# GateDriver.net
KiCad netlist of a schematic drawn in Altium Designer
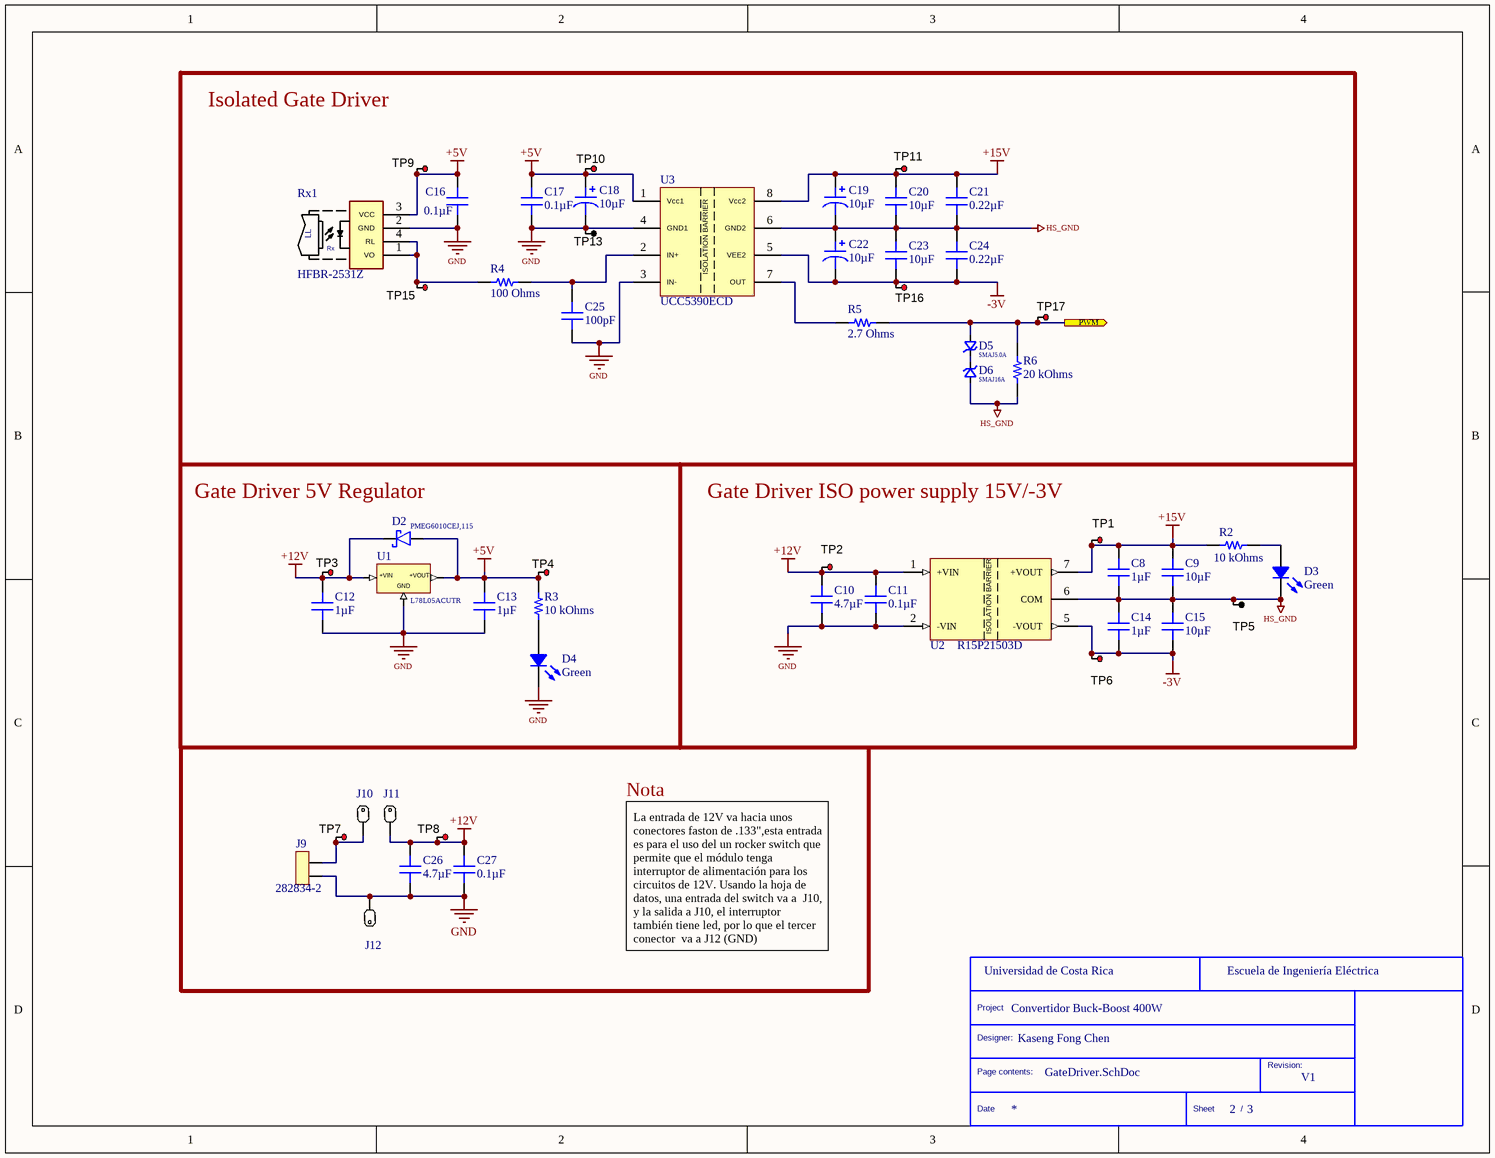
[diagram p0: GateDriver.SchDoc]

(export (version "E")
  (design (tool "Eeschema 10.0.6"))
  (components
    (comp (ref "C8")
      (value "1µF")
      (footprint "CAP 0603_1608")
      (description "CAP CER 1UF 50V X7R 0603")
      (fields (field (name "PART NUMBER") "UMK107AB7105KA-T") (field (name "MANUFACTURER") "Taiyo Yuden"))
      (libsource (lib "Celestial Altium Library - altium_library") (part "Capacitor"))
    )
    (comp (ref "C9")
      (value "10µF")
      (footprint "CAP 1206_3216 - 1.8MM")
      (description "CAP CER 10UF 25V X7R 1206")
      (fields (field (name "PART NUMBER") "TMK316AB7106KL-T") (field (name "MANUFACTURER") "Taiyo Yuden"))
      (libsource (lib "Celestial Altium Library - altium_library") (part "Capacitor"))
    )
    (comp (ref "C10")
      (value "4.7µF")
      (footprint "CAP 1206_3216 - 1.8MM")
      (description "CAP CER 4.7UF 50V X7R 1206")
      (fields (field (name "PART NUMBER") "UMK316AB7475KL-T") (field (name "MANUFACTURER") "Taiyo Yuden"))
      (libsource (lib "Celestial Altium Library - altium_library") (part "Capacitor"))
    )
    (comp (ref "C11")
      (value "0.1µF")
      (footprint "CAP 0603_1608")
      (description "CAP CER 0.1UF 50V X7R 0603")
      (fields (field (name "PART NUMBER") "C0603C104M5RACTU") (field (name "MANUFACTURER") "KEMET"))
      (libsource (lib "Celestial Altium Library - altium_library") (part "Capacitor"))
    )
    (comp (ref "C12")
      (value "1µF")
      (footprint "CAP 0603_1608")
      (description "CAP CER 1UF 25V X7R 0603")
      (fields (field (name "PART NUMBER") "TMK107B7105KA-T") (field (name "MANUFACTURER") "Taiyo Yuden"))
      (libsource (lib "Celestial Altium Library - altium_library") (part "Capacitor"))
    )
    (comp (ref "C13")
      (value "1µF")
      (footprint "CAP 0603_1608")
      (description "CAP CER 1UF 16V X7R 0603")
      (fields (field (name "PART NUMBER") "CC0603KRX7R7BB105") (field (name "MANUFACTURER") "Yageo"))
      (libsource (lib "Celestial Altium Library - altium_library") (part "Capacitor"))
    )
    (comp (ref "C14")
      (value "1µF")
      (footprint "CAP 0603_1608")
      (description "CAP CER 1UF 50V X7R 0603")
      (fields (field (name "PART NUMBER") "UMK107AB7105KA-T") (field (name "MANUFACTURER") "Taiyo Yuden"))
      (libsource (lib "Celestial Altium Library - altium_library") (part "Capacitor"))
    )
    (comp (ref "C15")
      (value "10µF")
      (footprint "CAP 1206_3216 - 1.8MM")
      (description "CAP CER 10UF 25V X7R 1206")
      (fields (field (name "PART NUMBER") "TMK316AB7106KL-T") (field (name "MANUFACTURER") "Taiyo Yuden"))
      (libsource (lib "Celestial Altium Library - altium_library") (part "Capacitor"))
    )
    (comp (ref "C16")
      (value "0.1µF")
      (footprint "CAP 0603_1608")
      (description "CAP CER 0.1UF 50V X7R 0603")
      (fields (field (name "PART NUMBER") "C0603C104M5RACTU") (field (name "MANUFACTURER") "KEMET"))
      (libsource (lib "Celestial Altium Library - altium_library") (part "Capacitor"))
    )
    (comp (ref "C17")
      (value "0.1µF")
      (footprint "CAP 0603_1608")
      (description "CAP CER 0.1UF 50V X7R 0603")
      (fields (field (name "PART NUMBER") "C0603C104M5RACTU") (field (name "MANUFACTURER") "KEMET"))
      (libsource (lib "Celestial Altium Library - altium_library") (part "Capacitor"))
    )
    (comp (ref "C18")
      (value "10µF")
      (footprint "CAP POL 2917_7343")
      (description "CAP TANT 10UF 10% 50V 2917")
      (fields (field (name "PART NUMBER") "T491D106K050AT") (field (name "MANUFACTURER") "KEMET"))
      (libsource (lib "Celestial Altium Library - altium_library") (part "Polarised Capacitor"))
    )
    (comp (ref "C19")
      (value "10µF")
      (footprint "CAP POL 2917_7343")
      (description "CAP TANT 10UF 10% 50V 2917")
      (fields (field (name "PART NUMBER") "T491D106K050AT") (field (name "MANUFACTURER") "KEMET"))
      (libsource (lib "Celestial Altium Library - altium_library") (part "Polarised Capacitor"))
    )
    (comp (ref "C20")
      (value "10µF")
      (footprint "CAP 1210_3225 - 2.8MM")
      (description "CAP CER 10UF 50V X7S 1210")
      (fields (field (name "PART NUMBER") "UMK325C7106MM-T") (field (name "MANUFACTURER") "Taiyo Yuden"))
      (libsource (lib "Celestial Altium Library - altium_library") (part "Capacitor"))
    )
    (comp (ref "C21")
      (value "0.22µF")
      (footprint "CAP 0805_2012")
      (description "CAP CER 0.22UF 50V X7R 0805")
      (fields (field (name "PART NUMBER") "UMK212B7224KG-T") (field (name "MANUFACTURER") "Taiyo Yuden"))
      (libsource (lib "Celestial Altium Library - altium_library") (part "Capacitor"))
    )
    (comp (ref "C22")
      (value "10µF")
      (footprint "CAP POL 2917_7343")
      (description "CAP TANT 10UF 10% 50V 2917")
      (fields (field (name "PART NUMBER") "T491D106K050AT") (field (name "MANUFACTURER") "KEMET"))
      (libsource (lib "Celestial Altium Library - altium_library") (part "Polarised Capacitor"))
    )
    (comp (ref "C23")
      (value "10µF")
      (footprint "CAP 1210_3225 - 2.8MM")
      (description "CAP CER 10UF 50V X7S 1210")
      (fields (field (name "PART NUMBER") "UMK325C7106MM-T") (field (name "MANUFACTURER") "Taiyo Yuden"))
      (libsource (lib "Celestial Altium Library - altium_library") (part "Capacitor"))
    )
    (comp (ref "C24")
      (value "0.22µF")
      (footprint "CAP 0805_2012")
      (description "CAP CER 0.22UF 50V X7R 0805")
      (fields (field (name "PART NUMBER") "UMK212B7224KG-T") (field (name "MANUFACTURER") "Taiyo Yuden"))
      (libsource (lib "Celestial Altium Library - altium_library") (part "Capacitor"))
    )
    (comp (ref "C25")
      (value "100pF")
      (footprint "CAP 0603_1608")
      (description "CAP CER 100PF 50V C0G/NP0 0603")
      (fields (field (name "PART NUMBER") "06035A101FAT2A") (field (name "MANUFACTURER") "AVX Corporation"))
      (libsource (lib "Celestial Altium Library - altium_library") (part "Capacitor"))
    )
    (comp (ref "C26")
      (value "4.7µF")
      (footprint "CAP 1206_3216 - 1.8MM")
      (description "CAP CER 4.7UF 50V X7R 1206")
      (fields (field (name "PART NUMBER") "UMK316AB7475KL-T") (field (name "MANUFACTURER") "Taiyo Yuden"))
      (libsource (lib "Celestial Altium Library - altium_library") (part "Capacitor"))
    )
    (comp (ref "C27")
      (value "0.1µF")
      (footprint "CAP 0603_1608")
      (description "CAP CER 0.1UF 50V X7R 0603")
      (fields (field (name "PART NUMBER") "C0603C104M5RACTU") (field (name "MANUFACTURER") "KEMET"))
      (libsource (lib "Celestial Altium Library - altium_library") (part "Capacitor"))
    )
    (comp (ref "D2")
      (value "PMEG6010CEJ,115")
      (footprint "SOD-323F")
      (description "PMEG6010CEH; PMEG6010CEJ - 1 A very low VF MEGA Schottky barrier rectifiers")
      (fields (field (name "MANUFACTURER") "Nexperia"))
      (libsource (lib "KasengLIb") (part "PMEG6010CEJ,115"))
    )
    (comp (ref "D3")
      (value "Green")
      (footprint "LED 0603_1608 GREEN")
      (description "LED GREEN CLEAR 0603 SMD")
      (fields (field (name "PART NUMBER") "150060GS75000") (field (name "MANUFACTURER") "Würth Elektronik"))
      (libsource (lib "Celestial Altium Library - altium_library") (part "LED"))
    )
    (comp (ref "D4")
      (value "Green")
      (footprint "LED 0603_1608 GREEN")
      (description "LED GREEN CLEAR 0603 SMD")
      (fields (field (name "PART NUMBER") "150060GS75000") (field (name "MANUFACTURER") "Würth Elektronik"))
      (libsource (lib "Celestial Altium Library - altium_library") (part "LED"))
    )
    (comp (ref "D5")
      (value "SMAJ5.0A")
      (footprint "DO214AC SMA")
      (description "BOURNS - SMAJ5.0A - TVS Diode, SMAJ Series, Unidirectional, 5 V, 9.2 V, DO-214AC (SMA), 2 Pins")
      (fields (field (name "MANUFACTURER") "Bourns"))
      (libsource (lib "KasengLIb") (part "SMAJ5.0A"))
    )
    (comp (ref "D6")
      (value "SMAJ16A")
      (footprint "DO214AC SMA")
      (description "TVS DIODE 16VWM 26VC DO214AC")
      (fields (field (name "MANUFACTURER") "Bourns"))
      (libsource (lib "KasengLIb") (part "SMAJ16A"))
    )
    (comp (ref "J9")
      (value "282834-2")
      (footprint "TE 282834-2")
      (description "TE CONNECTIVITY / BUCHANAN - 282834-2 - TERMINAL BLOCK, WIRE TO BRD, 2POS, 16AWG")
      (fields (field (name "MANUFACTURER") "TE Connectivity") (field (name "VOLTAGE") "150V"))
      (libsource (lib "kasengLib") (part "282834-2"))
    )
    (comp (ref "J10")
      (value "Faston .133")
      (description "CONN QC TAB 0.187 SOLDER")
      (fields
        (field (name "MANUFACTURER") "TE Connectivity")
        (field (name "MANUFACTURER PART NUMBER") "1217133-1")
      )
      (libsource (lib "KasengLIb") (part "1217133-1"))
    )
    (comp (ref "J11")
      (value "Faston .133")
      (description "CONN QC TAB 0.187 SOLDER")
      (fields
        (field (name "MANUFACTURER") "TE Connectivity")
        (field (name "MANUFACTURER PART NUMBER") "1217133-1")
      )
      (libsource (lib "KasengLIb") (part "1217133-1"))
    )
    (comp (ref "J12")
      (value "Faston .133")
      (description "CONN QC TAB 0.187 SOLDER")
      (fields
        (field (name "MANUFACTURER") "TE Connectivity")
        (field (name "MANUFACTURER PART NUMBER") "1217133-1")
      )
      (libsource (lib "KasengLIb") (part "1217133-1"))
    )
    (comp (ref "R2")
      (value "10 kOhms")
      (footprint "RES 0603_1608")
      (description "RES SMD 10K OHM 1% 1/10W 0603")
      (fields (field (name "PART NUMBER") "RC0603FR-0710KL") (field (name "MANUFACTURER") "Yageo"))
      (libsource (lib "Celestial Altium Library - altium_library") (part "Resistor"))
    )
    (comp (ref "R3")
      (value "10 kOhms")
      (footprint "RES 0603_1608")
      (description "RES SMD 10K OHM 1% 1/10W 0603")
      (fields (field (name "PART NUMBER") "RC0603FR-0710KL") (field (name "MANUFACTURER") "Yageo"))
      (libsource (lib "Celestial Altium Library - altium_library") (part "Resistor"))
    )
    (comp (ref "R4")
      (value "100 Ohms")
      (footprint "RES 0603_1608")
      (description "RES SMD 100 OHM 1% 1/10W 0603")
      (fields (field (name "PART NUMBER") "CRCW0603100RFKEAC") (field (name "MANUFACTURER") "Vishay Dale"))
      (libsource (lib "Celestial Altium Library - altium_library") (part "Resistor"))
    )
    (comp (ref "R5")
      (value "2.7 Ohms")
      (footprint "RES 1206_3216")
      (description "RES SMD 2.7 OHM 1% 3/4W 1206")
      (fields (field (name "PART NUMBER") "CRCW12062R70FKEAHP") (field (name "MANUFACTURER") "Vishay Dale"))
      (libsource (lib "Celestial Altium Library - altium_library") (part "Resistor"))
    )
    (comp (ref "R6")
      (value "20 kOhms")
      (footprint "RES 0603_1608")
      (description "RES SMD 20K OHM 1% 1/10W 0603")
      (fields (field (name "PART NUMBER") "RC0603FR-0720KL") (field (name "MANUFACTURER") "Yageo"))
      (libsource (lib "Celestial Altium Library - altium_library") (part "Resistor"))
    )
    (comp (ref "Rx1")
      (value "HFBR-2531Z")
      (footprint "HFBR-15X1V")
      (description "RX Optical Fiber 5MBd 6-Pin")
      (fields (field (name "MANUFACTURER") "Broadcom Avago"))
      (libsource (lib "KasengLIb") (part "HFBR-2531Z"))
    )
    (comp (ref "TP1")
      (value "5010")
      (footprint "Keystone5010")
      (description "Test Point, Multipurpose, Red, TH")
      (fields (field (name "MANUFACTURER") "Keystone") (field (name "PUBLISHER") "Texas Instruments"))
      (libsource (lib "kasengLib") (part "5010"))
    )
    (comp (ref "TP2")
      (value "5010")
      (footprint "Keystone5010")
      (description "Test Point, Multipurpose, Red, TH")
      (fields (field (name "MANUFACTURER") "Keystone") (field (name "PUBLISHER") "Texas Instruments"))
      (libsource (lib "kasengLib") (part "5010"))
    )
    (comp (ref "TP3")
      (value "5010")
      (footprint "Keystone5010")
      (description "Test Point, Multipurpose, Red, TH")
      (fields (field (name "MANUFACTURER") "Keystone") (field (name "PUBLISHER") "Texas Instruments"))
      (libsource (lib "kasengLib") (part "5010"))
    )
    (comp (ref "TP4")
      (value "5010")
      (footprint "Keystone5010")
      (description "Test Point, Multipurpose, Red, TH")
      (fields (field (name "MANUFACTURER") "Keystone") (field (name "PUBLISHER") "Texas Instruments"))
      (libsource (lib "kasengLib") (part "5010"))
    )
    (comp (ref "TP5")
      (value "5011")
      (footprint "Keystone5011")
      (description "Test Point, Multipurpose, Black, TH")
      (fields (field (name "MANUFACTURER") "Keystone") (field (name "PUBLISHER") "Texas Instruments"))
      (libsource (lib "kasengLib") (part "5011"))
    )
    (comp (ref "TP6")
      (value "5010")
      (footprint "Keystone5010")
      (description "Test Point, Multipurpose, Red, TH")
      (fields (field (name "MANUFACTURER") "Keystone") (field (name "PUBLISHER") "Texas Instruments"))
      (libsource (lib "kasengLib") (part "5010"))
    )
    (comp (ref "TP7")
      (value "5010")
      (footprint "Keystone5010")
      (description "Test Point, Multipurpose, Red, TH")
      (fields (field (name "MANUFACTURER") "Keystone") (field (name "PUBLISHER") "Texas Instruments"))
      (libsource (lib "kasengLib") (part "5010"))
    )
    (comp (ref "TP8")
      (value "5010")
      (footprint "Keystone5010")
      (description "Test Point, Multipurpose, Red, TH")
      (fields (field (name "MANUFACTURER") "Keystone") (field (name "PUBLISHER") "Texas Instruments"))
      (libsource (lib "kasengLib") (part "5010"))
    )
    (comp (ref "TP9")
      (value "5010")
      (footprint "Keystone5010")
      (description "Test Point, Multipurpose, Red, TH")
      (fields (field (name "MANUFACTURER") "Keystone") (field (name "PUBLISHER") "Texas Instruments"))
      (libsource (lib "kasengLib") (part "5010"))
    )
    (comp (ref "TP10")
      (value "5010")
      (footprint "Keystone5010")
      (description "Test Point, Multipurpose, Red, TH")
      (fields (field (name "MANUFACTURER") "Keystone") (field (name "PUBLISHER") "Texas Instruments"))
      (libsource (lib "kasengLib") (part "5010"))
    )
    (comp (ref "TP11")
      (value "5010")
      (footprint "Keystone5010")
      (description "Test Point, Multipurpose, Red, TH")
      (fields (field (name "MANUFACTURER") "Keystone") (field (name "PUBLISHER") "Texas Instruments"))
      (libsource (lib "kasengLib") (part "5010"))
    )
    (comp (ref "TP13")
      (value "5011")
      (footprint "Keystone5011")
      (description "Test Point, Multipurpose, Black, TH")
      (fields (field (name "MANUFACTURER") "Keystone") (field (name "PUBLISHER") "Texas Instruments"))
      (libsource (lib "kasengLib") (part "5011"))
    )
    (comp (ref "TP15")
      (value "5010")
      (footprint "Keystone5010")
      (description "Test Point, Multipurpose, Red, TH")
      (fields (field (name "MANUFACTURER") "Keystone") (field (name "PUBLISHER") "Texas Instruments"))
      (libsource (lib "kasengLib") (part "5010"))
    )
    (comp (ref "TP16")
      (value "5010")
      (footprint "Keystone5010")
      (description "Test Point, Multipurpose, Red, TH")
      (fields (field (name "MANUFACTURER") "Keystone") (field (name "PUBLISHER") "Texas Instruments"))
      (libsource (lib "kasengLib") (part "5010"))
    )
    (comp (ref "TP17")
      (value "5010")
      (footprint "Keystone5010")
      (description "Test Point, Multipurpose, Red, TH")
      (fields (field (name "MANUFACTURER") "Keystone") (field (name "PUBLISHER") "Texas Instruments"))
      (libsource (lib "kasengLib") (part "5010"))
    )
    (comp (ref "U1")
      (value "L78L05ACUTR")
      (footprint "VREG_L78L12ABUTR")
      (description "Voltage regulator; linear, fixed; 5V; 0.1A; SOT89; SMD; 0÷125°C")
      (fields (field (name "MANUFACTURER") "STMicroelectronics"))
      (libsource (lib "KasengLIb") (part "L78L05ACUTR"))
    )
    (comp (ref "U2")
      (value "R15P21503D")
      (footprint "CONV_R15P21503D")
      (description "2W DC/DC-Converter 'ECONOLINE' SIP7 6.4kV unreg; V. In: 15; V. Out: +15/-03; mA. Out: +93/-185")
      (fields (field (name "MANUFACTURER") "Recom"))
      (libsource (lib "KasengLIb") (part "R15P21503D"))
    )
    (comp (ref "U3")
      (value "UCC5390ECD")
      (footprint "SOIC127P599X175-8N")
      (fields (field (name "MANUFACTURER") "Texas Instruments"))
      (libsource (lib "kasengLib") (part "UCC5390ECD"))
    )
  )
  (nets
    (net (code "1") (name "+5V") (class "Default")
      (node (ref "C13") (pin "2") (pinfunction "2_2") (pintype "passive"))
      (node (ref "C16") (pin "2") (pinfunction "2_2") (pintype "passive"))
      (node (ref "C17") (pin "2") (pinfunction "2_2") (pintype "passive"))
      (node (ref "C18") (pin "1") (pinfunction "1_1") (pintype "passive"))
      (node (ref "D2") (pin "2") (pinfunction "2_2") (pintype "passive"))
      (node (ref "R3") (pin "1") (pinfunction "1_1") (pintype "passive"))
      (node (ref "Rx1") (pin "3") (pinfunction "VCC_3") (pintype "passive"))
      (node (ref "TP10") (pin "1") (pinfunction "1_1") (pintype "passive"))
      (node (ref "TP4") (pin "1") (pinfunction "1_1") (pintype "passive"))
      (node (ref "TP9") (pin "1") (pinfunction "1_1") (pintype "passive"))
      (node (ref "U1") (pin "1") (pinfunction "OUT_1") (pintype "output"))
      (node (ref "U3") (pin "1") (pinfunction "Vcc1_1") (pintype "passive"))
    )
    (net (code "2") (name "+12V") (class "Default")
      (node (ref "C10") (pin "2") (pinfunction "2_2") (pintype "passive"))
      (node (ref "C11") (pin "2") (pinfunction "2_2") (pintype "passive"))
      (node (ref "C12") (pin "2") (pinfunction "2_2") (pintype "passive"))
      (node (ref "C26") (pin "2") (pinfunction "2_2") (pintype "passive"))
      (node (ref "C27") (pin "2") (pinfunction "2_2") (pintype "passive"))
      (node (ref "D2") (pin "1") (pinfunction "1_1") (pintype "passive"))
      (node (ref "J11") (pin "1") (pinfunction "P1_1") (pintype "passive"))
      (node (ref "TP2") (pin "1") (pinfunction "1_1") (pintype "passive"))
      (node (ref "TP3") (pin "1") (pinfunction "1_1") (pintype "passive"))
      (node (ref "TP8") (pin "1") (pinfunction "1_1") (pintype "passive"))
      (node (ref "U1") (pin "3") (pinfunction "IN_3") (pintype "input"))
      (node (ref "U2") (pin "1") (pinfunction "+VIN_1") (pintype "input"))
    )
    (net (code "3") (name "+15V") (class "Default")
      (node (ref "C19") (pin "1") (pinfunction "1_1") (pintype "passive"))
      (node (ref "C20") (pin "1") (pinfunction "1_1") (pintype "passive"))
      (node (ref "C21") (pin "1") (pinfunction "1_1") (pintype "passive"))
      (node (ref "C8") (pin "2") (pinfunction "2_2") (pintype "passive"))
      (node (ref "C9") (pin "2") (pinfunction "2_2") (pintype "passive"))
      (node (ref "R2") (pin "1") (pinfunction "1_1") (pintype "passive"))
      (node (ref "TP1") (pin "1") (pinfunction "1_1") (pintype "passive"))
      (node (ref "TP11") (pin "1") (pinfunction "1_1") (pintype "passive"))
      (node (ref "U2") (pin "7") (pinfunction "+VOUT_7") (pintype "output"))
      (node (ref "U3") (pin "8") (pinfunction "Vcc2_8") (pintype "passive"))
    )
    (net (code "4") (name "-3V") (class "Default")
      (node (ref "C14") (pin "1") (pinfunction "1_1") (pintype "passive"))
      (node (ref "C15") (pin "1") (pinfunction "1_1") (pintype "passive"))
      (node (ref "C22") (pin "2") (pinfunction "2_2") (pintype "passive"))
      (node (ref "C23") (pin "2") (pinfunction "2_2") (pintype "passive"))
      (node (ref "C24") (pin "2") (pinfunction "2_2") (pintype "passive"))
      (node (ref "TP16") (pin "1") (pinfunction "1_1") (pintype "passive"))
      (node (ref "TP6") (pin "1") (pinfunction "1_1") (pintype "passive"))
      (node (ref "U2") (pin "5") (pinfunction "-VOUT_5") (pintype "output"))
      (node (ref "U3") (pin "5") (pinfunction "VEE2_5") (pintype "passive"))
    )
    (net (code "5") (name "/PWM") (class "Default")
      (node (ref "D5") (pin "2") (pinfunction "2_2") (pintype "passive"))
      (node (ref "R5") (pin "2") (pinfunction "2_2") (pintype "passive"))
      (node (ref "R6") (pin "2") (pinfunction "2_2") (pintype "passive"))
      (node (ref "TP17") (pin "1") (pinfunction "1_1") (pintype "passive"))
    )
    (net (code "6") (name "GND") (class "Default")
      (node (ref "C10") (pin "1") (pinfunction "1_1") (pintype "passive"))
      (node (ref "C11") (pin "1") (pinfunction "1_1") (pintype "passive"))
      (node (ref "C12") (pin "1") (pinfunction "1_1") (pintype "passive"))
      (node (ref "C13") (pin "1") (pinfunction "1_1") (pintype "passive"))
      (node (ref "C16") (pin "1") (pinfunction "1_1") (pintype "passive"))
      (node (ref "C17") (pin "1") (pinfunction "1_1") (pintype "passive"))
      (node (ref "C18") (pin "2") (pinfunction "2_2") (pintype "passive"))
      (node (ref "C25") (pin "1") (pinfunction "1_1") (pintype "passive"))
      (node (ref "C26") (pin "1") (pinfunction "1_1") (pintype "passive"))
      (node (ref "C27") (pin "1") (pinfunction "1_1") (pintype "passive"))
      (node (ref "D4") (pin "2") (pinfunction "2_2") (pintype "passive"))
      (node (ref "J12") (pin "1") (pinfunction "P1_1") (pintype "passive"))
      (node (ref "J9") (pin "2") (pinfunction "2_2") (pintype "passive"))
      (node (ref "Rx1") (pin "2") (pinfunction "GND_2") (pintype "power_in"))
      (node (ref "TP13") (pin "1") (pinfunction "1_1") (pintype "passive"))
      (node (ref "U1") (pin "2") (pinfunction "GND_2") (pintype "input"))
      (node (ref "U2") (pin "2") (pinfunction "-VIN_2") (pintype "input"))
      (node (ref "U3") (pin "3") (pinfunction "IN-_3") (pintype "passive"))
      (node (ref "U3") (pin "4") (pinfunction "GND1_4") (pintype "passive"))
    )
    (net (code "7") (name "HS_GND") (class "Default")
      (node (ref "C14") (pin "2") (pinfunction "2_2") (pintype "passive"))
      (node (ref "C15") (pin "2") (pinfunction "2_2") (pintype "passive"))
      (node (ref "C19") (pin "2") (pinfunction "2_2") (pintype "passive"))
      (node (ref "C20") (pin "2") (pinfunction "2_2") (pintype "passive"))
      (node (ref "C21") (pin "2") (pinfunction "2_2") (pintype "passive"))
      (node (ref "C22") (pin "1") (pinfunction "1_1") (pintype "passive"))
      (node (ref "C23") (pin "1") (pinfunction "1_1") (pintype "passive"))
      (node (ref "C24") (pin "1") (pinfunction "1_1") (pintype "passive"))
      (node (ref "C8") (pin "1") (pinfunction "1_1") (pintype "passive"))
      (node (ref "C9") (pin "1") (pinfunction "1_1") (pintype "passive"))
      (node (ref "D3") (pin "2") (pinfunction "2_2") (pintype "passive"))
      (node (ref "D6") (pin "2") (pinfunction "2_2") (pintype "passive"))
      (node (ref "R6") (pin "1") (pinfunction "1_1") (pintype "passive"))
      (node (ref "TP5") (pin "1") (pinfunction "1_1") (pintype "passive"))
      (node (ref "U2") (pin "6") (pinfunction "COM_6") (pintype "power_in"))
      (node (ref "U3") (pin "6") (pinfunction "GND2_6") (pintype "passive"))
    )
    (net (code "8") (name "Net-(D3-Pad1)") (class "Default")
      (node (ref "D3") (pin "1") (pinfunction "1_1") (pintype "passive"))
      (node (ref "R2") (pin "2") (pinfunction "2_2") (pintype "passive"))
    )
    (net (code "9") (name "Net-(D4-Pad1)") (class "Default")
      (node (ref "D4") (pin "1") (pinfunction "1_1") (pintype "passive"))
      (node (ref "R3") (pin "2") (pinfunction "2_2") (pintype "passive"))
    )
    (net (code "10") (name "Net-(D5-Pad1)") (class "Default")
      (node (ref "D5") (pin "1") (pinfunction "1_1") (pintype "passive"))
      (node (ref "D6") (pin "1") (pinfunction "1_1") (pintype "passive"))
    )
    (net (code "11") (name "Net-(J10-P1)") (class "Default")
      (node (ref "J10") (pin "1") (pinfunction "P1_1") (pintype "passive"))
      (node (ref "J9") (pin "1") (pinfunction "1_1") (pintype "passive"))
      (node (ref "TP7") (pin "1") (pinfunction "1_1") (pintype "passive"))
    )
    (net (code "12") (name "Net-(Rx1-RL)") (class "Default")
      (node (ref "R4") (pin "1") (pinfunction "1_1") (pintype "passive"))
      (node (ref "Rx1") (pin "1") (pinfunction "VO_1") (pintype "passive"))
      (node (ref "Rx1") (pin "4") (pinfunction "RL_4") (pintype "passive"))
      (node (ref "TP15") (pin "1") (pinfunction "1_1") (pintype "passive"))
    )
    (net (code "13") (name "Net-(U3-IN+)") (class "Default")
      (node (ref "C25") (pin "2") (pinfunction "2_2") (pintype "passive"))
      (node (ref "R4") (pin "2") (pinfunction "2_2") (pintype "passive"))
      (node (ref "U3") (pin "2") (pinfunction "IN+_2") (pintype "passive"))
    )
    (net (code "14") (name "Net-(U3-OUT)") (class "Default")
      (node (ref "R5") (pin "1") (pinfunction "1_1") (pintype "passive"))
      (node (ref "U3") (pin "7") (pinfunction "OUT_7") (pintype "passive"))
    )
  )
)
